# ph.net
KiCad netlist of a schematic drawn in Altium Designer
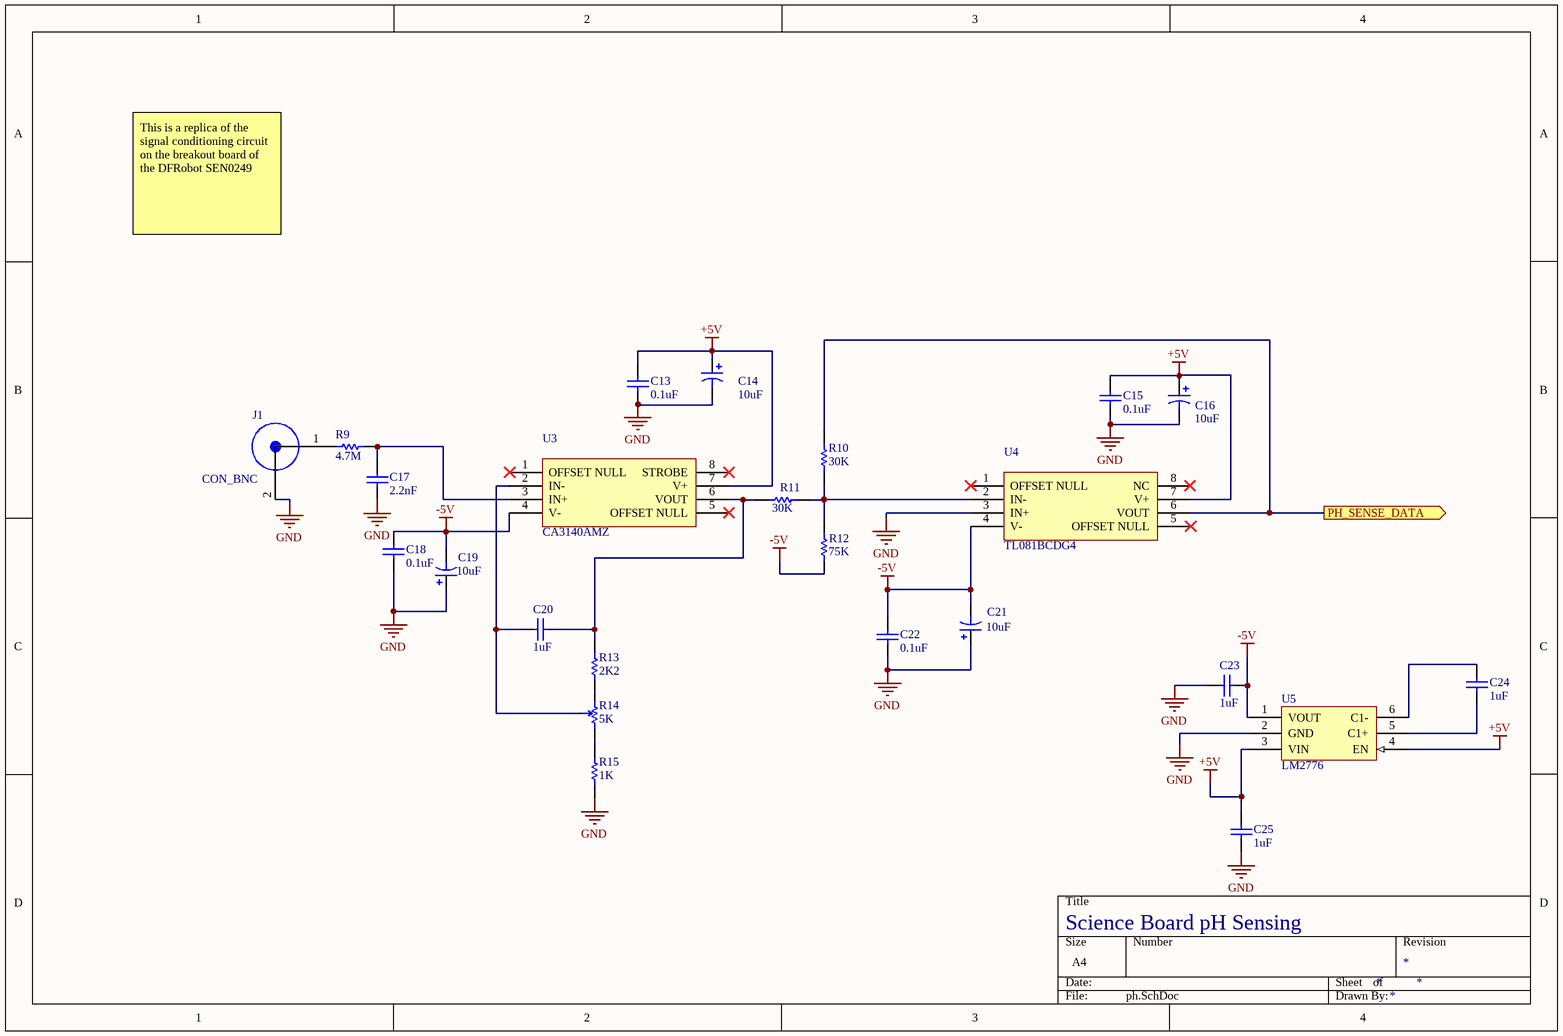
[diagram p0: ph.SchDoc]

(export (version "E")
  (design (tool "Eeschema 10.0.6"))
  (components
    (comp (ref "C13")
      (value "0.1uF")
      (footprint "CAPC0603(1608)55_N")
      (description "CAP CER 0.1UF 50V X7R 0603")
      (fields (field (name "MANUFACTURER") "Yageo") (field (name "MPN") "CC0603KRX7R9BB104"))
      (libsource (lib "UWRT_Schematic_Library_2019") (part "CAP_0.1uF_50V_0603"))
    )
    (comp (ref "C14")
      (value "10uF")
      (footprint "AVX-CAPC3528_V")
      (description "Capacitor, Tantalum, 10uF 10% 20V MCCT-B (3528)")
      (fields (field (name "PART NUMBER") "CC0603MRX5R6BB106") (field (name "MANUFACTURER") "Yageo"))
      (libsource (lib "UWRT_Schematic_Library_2019") (part "CAP_10uF_0603_POL"))
    )
    (comp (ref "C15")
      (value "0.1uF")
      (footprint "CAPC0603(1608)55_N")
      (description "CAP CER 0.1UF 50V X7R 0603")
      (fields (field (name "MANUFACTURER") "Yageo") (field (name "MPN") "CC0603KRX7R9BB104"))
      (libsource (lib "UWRT_Schematic_Library_2019") (part "CAP_0.1uF_50V_0603"))
    )
    (comp (ref "C16")
      (value "10uF")
      (footprint "AVX-CAPC3528_V")
      (description "Capacitor, Tantalum, 10uF 10% 20V MCCT-B (3528)")
      (fields (field (name "PART NUMBER") "CC0603MRX5R6BB106") (field (name "MANUFACTURER") "Yageo"))
      (libsource (lib "UWRT_Schematic_Library_2019") (part "CAP_10uF_0603_POL"))
    )
    (comp (ref "C17")
      (value "2.2nF")
      (footprint "CAPC0603(1608)55_N")
      (description "CAP CER 2.2NF 25V X7R 0603")
      (fields (field (name "MANUFACTURER") "Yageo") (field (name "MPN") "CC0603KRX7R8BB222"))
      (libsource (lib "UWRT_Schematic_Library_2019") (part "CAP_2.2nF_0603"))
    )
    (comp (ref "C18")
      (value "0.1uF")
      (footprint "CAPC0603(1608)55_N")
      (description "CAP CER 0.1UF 50V X7R 0603")
      (fields (field (name "MANUFACTURER") "Yageo") (field (name "MPN") "CC0603KRX7R9BB104"))
      (libsource (lib "UWRT_Schematic_Library_2019") (part "CAP_0.1uF_50V_0603"))
    )
    (comp (ref "C19")
      (value "10uF")
      (footprint "AVX-CAPC3528_V")
      (description "Capacitor, Tantalum, 10uF 10% 20V MCCT-B (3528)")
      (fields (field (name "PART NUMBER") "CC0603MRX5R6BB106") (field (name "MANUFACTURER") "Yageo"))
      (libsource (lib "UWRT_Schematic_Library_2019") (part "CAP_10uF_0603_POL"))
    )
    (comp (ref "C20")
      (value "1uF")
      (footprint "CAPC0603(1608)55_N")
      (description "CAP CER 1UF 16V Y5V 0603")
      (fields (field (name "MANUFACTURER") "Yageo") (field (name "MPN") "CC0603ZRY5V7BB105"))
      (libsource (lib "UWRT_Schematic_Library_2019") (part "CAP_1uF_16V_0603"))
    )
    (comp (ref "C21")
      (value "10uF")
      (footprint "AVX-CAPC3528_V")
      (description "Capacitor, Tantalum, 10uF 10% 20V MCCT-B (3528)")
      (fields (field (name "PART NUMBER") "CC0603MRX5R6BB106") (field (name "MANUFACTURER") "Yageo"))
      (libsource (lib "UWRT_Schematic_Library_2019") (part "CAP_10uF_0603_POL"))
    )
    (comp (ref "C22")
      (value "0.1uF")
      (footprint "CAPC0603(1608)55_N")
      (description "CAP CER 0.1UF 50V X7R 0603")
      (fields (field (name "MANUFACTURER") "Yageo") (field (name "MPN") "CC0603KRX7R9BB104"))
      (libsource (lib "UWRT_Schematic_Library_2019") (part "CAP_0.1uF_50V_0603"))
    )
    (comp (ref "C23")
      (value "1uF")
      (footprint "CAPC0603(1608)55_N")
      (description "CAP CER 1UF 16V Y5V 0603")
      (fields (field (name "MANUFACTURER") "Yageo") (field (name "MPN") "CC0603ZRY5V7BB105"))
      (libsource (lib "UWRT_Schematic_Library_2019") (part "CAP_1uF_16V_0603"))
    )
    (comp (ref "C24")
      (value "1uF")
      (footprint "CAPC0603(1608)55_N")
      (description "CAP CER 1UF 16V Y5V 0603")
      (fields (field (name "MANUFACTURER") "Yageo") (field (name "MPN") "CC0603ZRY5V7BB105"))
      (libsource (lib "UWRT_Schematic_Library_2019") (part "CAP_1uF_16V_0603"))
    )
    (comp (ref "C25")
      (value "1uF")
      (footprint "CAPC0603(1608)55_N")
      (description "CAP CER 1UF 16V Y5V 0603")
      (fields (field (name "MANUFACTURER") "Yageo") (field (name "MPN") "CC0603ZRY5V7BB105"))
      (libsource (lib "UWRT_Schematic_Library_2019") (part "CAP_1uF_16V_0603"))
    )
    (comp (ref "J1")
      (value "CON_BNC")
      (footprint "1-1337543-0")
      (fields
        (field (name "MANUFACTURER") "TE Connectivity")
        (field (name "MPN") "1-1337543-0")
        (field (name "DIGIKEY PART NUMBER") "A97553-ND")
      )
      (libsource (lib "UWRT_Schematic_Library_2019") (part "CON_BNC"))
    )
    (comp (ref "R9")
      (value "4.7M")
      (footprint "RESC0603(1608)_N")
      (description "RES SMD 4.7M OHM 1% 1/10W 0603")
      (fields (field (name "TOLERANCE") "1%") (field (name "MANUFACTURER") "Yageo"))
      (libsource (lib "UWRT_Schematic_Library_2019") (part "RES_4M7_0603"))
    )
    (comp (ref "R10")
      (value "30K")
      (footprint "RESC0603(1608)_N")
      (description "RES SMD 30K OHM 0.5% 1/10W 0603")
      (fields (field (name "MANUFACTURER") "Yageo") (field (name "TOLERANCE") "0.5%"))
      (libsource (lib "UWRT_Schematic_Library_2019") (part "RES_30K_0603"))
    )
    (comp (ref "R11")
      (value "30K")
      (footprint "RESC0603(1608)_N")
      (description "RES SMD 30K OHM 0.5% 1/10W 0603")
      (fields (field (name "MANUFACTURER") "Yageo") (field (name "TOLERANCE") "0.5%"))
      (libsource (lib "UWRT_Schematic_Library_2019") (part "RES_30K_0603"))
    )
    (comp (ref "R12")
      (value "75K")
      (footprint "RESC0603(1608)_N")
      (description "RES SMD 75K OHM 0.5% 1/10W 0603")
      (fields (field (name "MANUFACTURER") "Yageo") (field (name "TOLERANCE") "0.5%"))
      (libsource (lib "UWRT_Schematic_Library_2019") (part "RES_75K_0603"))
    )
    (comp (ref "R13")
      (value "2K2")
      (footprint "RESC0603(1608)_N")
      (description "RES SMD 2.2K OHM 1% 1/10W 0603")
      (fields (field (name "MANUFACTURER") "Yageo") (field (name "TOLERANCE") "1%"))
      (libsource (lib "UWRT_Schematic_Library_2019") (part "RES_2K2_0603"))
    )
    (comp (ref "R14")
      (value "5K")
      (footprint "3362P-1-502LF")
      (description "TRIMMER 5K OHM 0.5W PC PIN TOP")
      (fields (field (name "MANUFACTURER") "Bourns Inc.") (field (name "TOLERANCE") "10%"))
      (libsource (lib "UWRT_Schematic_Library_2019") (part "POT_5K"))
    )
    (comp (ref "R15")
      (value "1K")
      (footprint "RESC0603(1608)_N")
      (description "RES SMD 1K OHM 5% 1/10W 0603")
      (fields (field (name "TOLERANCE") "5%") (field (name "MANUFACTURER") "Yageo"))
      (libsource (lib "UWRT_Schematic_Library_2019") (part "RES_1K_0603"))
    )
    (comp (ref "U3")
      (value "CA3140AMZ")
      (footprint "CA3140AMZ")
      (description "4.5MHz, BiMOS Operational Amplifier with MOSFET Input/Bipolar Output")
      (fields
        (field (name "DIGIKEY PART NUMBER") "CA3140AMZ-ND")
        (field (name "MANUFACTURER") "Renesas Electronics America Inc.")
      )
      (libsource (lib "UWRT_Schematic_Library_2019") (part "CA3140AMZ"))
    )
    (comp (ref "U4")
      (value "TL081BCDG4")
      (footprint "TL081BCDG4")
      (description "IC OPAMP JFET 3MHZ 8SOIC")
      (fields (field (name "MPN") "TL081BCD") (field (name "DIGIKEY PART NUMBER") "296-34259-5-ND"))
      (libsource (lib "UWRT_Schematic_Library_2019") (part "TL081BCDG4"))
    )
    (comp (ref "U5")
      (value "LM2776")
      (footprint "SOT23-6")
      (description "LM2776 Switched Capacitor Inverter")
      (fields (field (name "MPN") "LM2776DBVR") (field (name "DIGIKEY PART NUMBER") "296-43957-1-ND"))
      (libsource (lib "UWRT_Schematic_Library_2019") (part "LM2776"))
    )
  )
  (nets
    (net (code "1") (name "+5V") (class "Default")
      (node (ref "C13") (pin "2") (pinfunction "2_2") (pintype "passive"))
      (node (ref "C14") (pin "1") (pinfunction "1_1") (pintype "passive"))
      (node (ref "C15") (pin "2") (pinfunction "2_2") (pintype "passive"))
      (node (ref "C16") (pin "1") (pinfunction "1_1") (pintype "passive"))
      (node (ref "C25") (pin "2") (pinfunction "2_2") (pintype "passive"))
      (node (ref "U3") (pin "7") (pinfunction "V+_7") (pintype "passive"))
      (node (ref "U4") (pin "7") (pinfunction "V+_7") (pintype "passive"))
      (node (ref "U5") (pin "3") (pinfunction "VIN_3") (pintype "power_in"))
      (node (ref "U5") (pin "4") (pinfunction "EN_4") (pintype "input"))
    )
    (net (code "2") (name "-5V") (class "Default")
      (node (ref "C18") (pin "2") (pinfunction "2_2") (pintype "passive"))
      (node (ref "C19") (pin "2") (pinfunction "2_2") (pintype "passive"))
      (node (ref "C21") (pin "2") (pinfunction "2_2") (pintype "passive"))
      (node (ref "C22") (pin "2") (pinfunction "2_2") (pintype "passive"))
      (node (ref "C23") (pin "1") (pinfunction "1_1") (pintype "passive"))
      (node (ref "R12") (pin "1") (pinfunction "1_1") (pintype "passive"))
      (node (ref "U3") (pin "4") (pinfunction "V-_4") (pintype "passive"))
      (node (ref "U4") (pin "4") (pinfunction "V-_4") (pintype "passive"))
      (node (ref "U5") (pin "1") (pinfunction "VOUT_1") (pintype "power_in"))
    )
    (net (code "3") (name "/PH_SENSE_DATA") (class "Default")
      (node (ref "R10") (pin "2") (pinfunction "2_2") (pintype "passive"))
      (node (ref "U4") (pin "6") (pinfunction "VOUT_6") (pintype "passive"))
    )
    (net (code "4") (name "GND") (class "Default")
      (node (ref "C13") (pin "1") (pinfunction "1_1") (pintype "passive"))
      (node (ref "C14") (pin "2") (pinfunction "2_2") (pintype "passive"))
      (node (ref "C15") (pin "1") (pinfunction "1_1") (pintype "passive"))
      (node (ref "C16") (pin "2") (pinfunction "2_2") (pintype "passive"))
      (node (ref "C17") (pin "1") (pinfunction "1_1") (pintype "passive"))
      (node (ref "C18") (pin "1") (pinfunction "1_1") (pintype "passive"))
      (node (ref "C19") (pin "1") (pinfunction "1_1") (pintype "passive"))
      (node (ref "C21") (pin "1") (pinfunction "1_1") (pintype "passive"))
      (node (ref "C22") (pin "1") (pinfunction "1_1") (pintype "passive"))
      (node (ref "C23") (pin "2") (pinfunction "2_2") (pintype "passive"))
      (node (ref "C25") (pin "1") (pinfunction "1_1") (pintype "passive"))
      (node (ref "J1") (pin "2") (pintype "passive"))
      (node (ref "R15") (pin "1") (pinfunction "1_1") (pintype "passive"))
      (node (ref "U4") (pin "3") (pinfunction "IN+_3") (pintype "passive"))
      (node (ref "U5") (pin "2") (pinfunction "GND_2") (pintype "passive"))
    )
    (net (code "5") (name "Net-(J1-Pad1)") (class "Default")
      (node (ref "J1") (pin "1") (pintype "passive"))
      (node (ref "R9") (pin "1") (pinfunction "1_1") (pintype "passive"))
    )
    (net (code "6") (name "Net-(R13-Pad1)") (class "Default")
      (node (ref "R13") (pin "1") (pinfunction "1_1") (pintype "passive"))
      (node (ref "R14") (pin "1") (pinfunction "1_1") (pintype "passive"))
    )
    (net (code "7") (name "Net-(R14-Pad2)") (class "Default")
      (node (ref "R14") (pin "2") (pinfunction "2_2") (pintype "passive"))
      (node (ref "R15") (pin "2") (pinfunction "2_2") (pintype "passive"))
    )
    (net (code "8") (name "Net-(U3-IN+)") (class "Default")
      (node (ref "C17") (pin "2") (pinfunction "2_2") (pintype "passive"))
      (node (ref "R9") (pin "2") (pinfunction "2_2") (pintype "passive"))
      (node (ref "U3") (pin "3") (pinfunction "IN+_3") (pintype "passive"))
    )
    (net (code "9") (name "Net-(U3-IN-)") (class "Default")
      (node (ref "C20") (pin "1") (pinfunction "1_1") (pintype "passive"))
      (node (ref "R14") (pin "3") (pinfunction "3_3") (pintype "passive"))
      (node (ref "U3") (pin "2") (pinfunction "IN-_2") (pintype "passive"))
    )
    (net (code "10") (name "Net-(U3-VOUT)") (class "Default")
      (node (ref "C20") (pin "2") (pinfunction "2_2") (pintype "passive"))
      (node (ref "R11") (pin "1") (pinfunction "1_1") (pintype "passive"))
      (node (ref "R13") (pin "2") (pinfunction "2_2") (pintype "passive"))
      (node (ref "U3") (pin "6") (pinfunction "VOUT_6") (pintype "passive"))
    )
    (net (code "11") (name "Net-(U4-IN-)") (class "Default")
      (node (ref "R10") (pin "1") (pinfunction "1_1") (pintype "passive"))
      (node (ref "R11") (pin "2") (pinfunction "2_2") (pintype "passive"))
      (node (ref "R12") (pin "2") (pinfunction "2_2") (pintype "passive"))
      (node (ref "U4") (pin "2") (pinfunction "IN-_2") (pintype "passive"))
    )
    (net (code "12") (name "Net-(U5-C1+)") (class "Default")
      (node (ref "C24") (pin "1") (pinfunction "1_1") (pintype "passive"))
      (node (ref "U5") (pin "5") (pinfunction "C1+_5") (pintype "power_in"))
    )
    (net (code "13") (name "Net-(U5-C1-)") (class "Default")
      (node (ref "C24") (pin "2") (pinfunction "2_2") (pintype "passive"))
      (node (ref "U5") (pin "6") (pinfunction "C1-_6") (pintype "power_in"))
    )
    (net (code "14") (name "unconnected-(U3-OFFSET_NULL-Pad1)") (class "Default")
      (node (ref "U3") (pin "1") (pinfunction "OFFSET_NULL_1") (pintype "passive"))
    )
    (net (code "15") (name "unconnected-(U3-OFFSET_NULL-Pad5)") (class "Default")
      (node (ref "U3") (pin "5") (pinfunction "OFFSET_NULL_5") (pintype "passive+no_connect"))
    )
    (net (code "16") (name "unconnected-(U3-STROBE-Pad8)") (class "Default")
      (node (ref "U3") (pin "8") (pinfunction "STROBE_8") (pintype "passive+no_connect"))
    )
    (net (code "17") (name "unconnected-(U4-NC-Pad8)") (class "Default")
      (node (ref "U4") (pin "8") (pinfunction "NC_8") (pintype "passive"))
    )
    (net (code "18") (name "unconnected-(U4-OFFSET_NULL-Pad1)") (class "Default")
      (node (ref "U4") (pin "1") (pinfunction "OFFSET_NULL_1") (pintype "passive+no_connect"))
    )
    (net (code "19") (name "unconnected-(U4-OFFSET_NULL-Pad5)") (class "Default")
      (node (ref "U4") (pin "5") (pinfunction "OFFSET_NULL_5") (pintype "passive"))
    )
  )
)
